# main.net
KiCad netlist of a schematic drawn in EAGLE
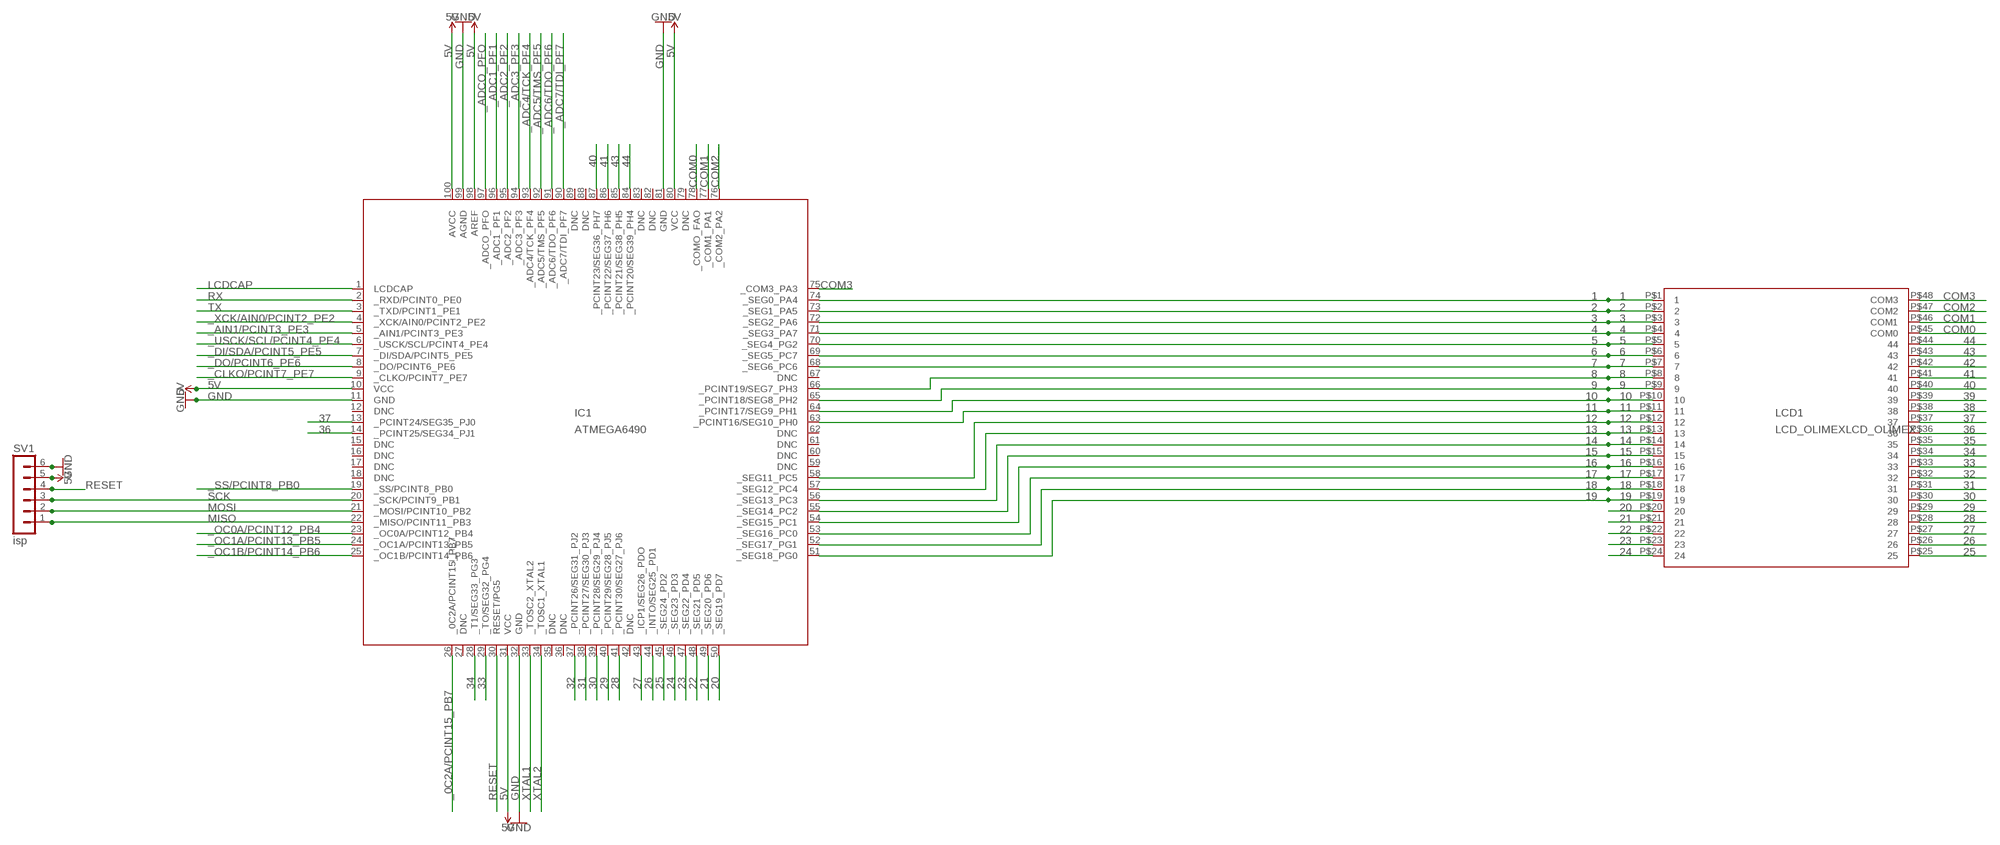
[diagram p0: schematic, sheet 1]

(export (version "E")
  (design (tool "Eeschema 10.0.6"))
  (components
    (comp (ref "IC1")
      (value "ATMEGA6490")
      (footprint "eagle-import:TQFP100")
      (libsource (lib "eagle-import") (part "ATMEGA6490"))
    )
    (comp (ref "LCD1")
      (value "LCD_OLIMEXLCD_OLIMEX")
      (footprint "eagle-import:LCD_OLIMEX")
      (libsource (lib "eagle-import") (part "LCD_OLIMEXLCD_OLIMEX"))
    )
    (comp (ref "SV1")
      (value "isp")
      (footprint "eagle-import:MA06-1")
      (libsource (lib "eagle-import") (part "MA06-1"))
    )
  )
  (nets
    (net (code "1") (name "/1") (class "Default")
      (node (ref "IC1") (pin "74") (pinfunction "_SEG0_PA4_74") (pintype "bidirectional"))
      (node (ref "LCD1") (pin "P$1") (pinfunction "1_P$1") (pintype "bidirectional"))
    )
    (net (code "2") (name "/2") (class "Default")
      (node (ref "IC1") (pin "73") (pinfunction "_SEG1_PA5_73") (pintype "bidirectional"))
      (node (ref "LCD1") (pin "P$2") (pinfunction "2_P$2") (pintype "bidirectional"))
    )
    (net (code "3") (name "/3") (class "Default")
      (node (ref "IC1") (pin "72") (pinfunction "_SEG2_PA6_72") (pintype "bidirectional"))
      (node (ref "LCD1") (pin "P$3") (pinfunction "3_P$3") (pintype "bidirectional"))
    )
    (net (code "4") (name "/4") (class "Default")
      (node (ref "IC1") (pin "71") (pinfunction "_SEG3_PA7_71") (pintype "bidirectional"))
      (node (ref "LCD1") (pin "P$4") (pinfunction "4_P$4") (pintype "bidirectional"))
    )
    (net (code "5") (name "/5") (class "Default")
      (node (ref "IC1") (pin "70") (pinfunction "_SEG4_PG2_70") (pintype "bidirectional"))
      (node (ref "LCD1") (pin "P$5") (pinfunction "5_P$5") (pintype "bidirectional"))
    )
    (net (code "6") (name "/6") (class "Default")
      (node (ref "IC1") (pin "69") (pinfunction "_SEG5_PC7_69") (pintype "bidirectional"))
      (node (ref "LCD1") (pin "P$6") (pinfunction "6_P$6") (pintype "bidirectional"))
    )
    (net (code "7") (name "/7") (class "Default")
      (node (ref "IC1") (pin "68") (pinfunction "_SEG6_PC6_68") (pintype "bidirectional"))
      (node (ref "LCD1") (pin "P$7") (pinfunction "7_P$7") (pintype "bidirectional"))
    )
    (net (code "8") (name "/8") (class "Default")
      (node (ref "IC1") (pin "66") (pinfunction "_PCINT19/SEG7_PH3_66") (pintype "bidirectional"))
      (node (ref "LCD1") (pin "P$8") (pinfunction "8_P$8") (pintype "bidirectional"))
    )
    (net (code "9") (name "/9") (class "Default")
      (node (ref "IC1") (pin "65") (pinfunction "_PCINT18/SEG8_PH2_65") (pintype "bidirectional"))
      (node (ref "LCD1") (pin "P$9") (pinfunction "9_P$9") (pintype "bidirectional"))
    )
    (net (code "10") (name "/10") (class "Default")
      (node (ref "IC1") (pin "64") (pinfunction "_PCINT17/SEG9_PH1_64") (pintype "bidirectional"))
      (node (ref "LCD1") (pin "P$10") (pinfunction "10_P$10") (pintype "bidirectional"))
    )
    (net (code "11") (name "/11") (class "Default")
      (node (ref "IC1") (pin "63") (pinfunction "_PCINT16/SEG10_PH0_63") (pintype "bidirectional"))
      (node (ref "LCD1") (pin "P$11") (pinfunction "11_P$11") (pintype "bidirectional"))
    )
    (net (code "12") (name "/12") (class "Default")
      (node (ref "IC1") (pin "58") (pinfunction "_SEG11_PC5_58") (pintype "bidirectional"))
      (node (ref "LCD1") (pin "P$12") (pinfunction "12_P$12") (pintype "bidirectional"))
    )
    (net (code "13") (name "/13") (class "Default")
      (node (ref "IC1") (pin "57") (pinfunction "_SEG12_PC4_57") (pintype "bidirectional"))
      (node (ref "LCD1") (pin "P$13") (pinfunction "13_P$13") (pintype "bidirectional"))
    )
    (net (code "14") (name "/14") (class "Default")
      (node (ref "IC1") (pin "56") (pinfunction "_SEG13_PC3_56") (pintype "bidirectional"))
      (node (ref "LCD1") (pin "P$14") (pinfunction "14_P$14") (pintype "bidirectional"))
    )
    (net (code "15") (name "/15") (class "Default")
      (node (ref "IC1") (pin "55") (pinfunction "_SEG14_PC2_55") (pintype "bidirectional"))
      (node (ref "LCD1") (pin "P$15") (pinfunction "15_P$15") (pintype "bidirectional"))
    )
    (net (code "16") (name "/16") (class "Default")
      (node (ref "IC1") (pin "54") (pinfunction "_SEG15_PC1_54") (pintype "bidirectional"))
      (node (ref "LCD1") (pin "P$16") (pinfunction "16_P$16") (pintype "bidirectional"))
    )
    (net (code "17") (name "/17") (class "Default")
      (node (ref "IC1") (pin "53") (pinfunction "_SEG16_PC0_53") (pintype "bidirectional"))
      (node (ref "LCD1") (pin "P$17") (pinfunction "17_P$17") (pintype "bidirectional"))
    )
    (net (code "18") (name "/18") (class "Default")
      (node (ref "IC1") (pin "52") (pinfunction "_SEG17_PG1_52") (pintype "bidirectional"))
      (node (ref "LCD1") (pin "P$18") (pinfunction "18_P$18") (pintype "bidirectional"))
    )
    (net (code "19") (name "/19") (class "Default")
      (node (ref "IC1") (pin "51") (pinfunction "_SEG18_PG0_51") (pintype "bidirectional"))
      (node (ref "LCD1") (pin "P$19") (pinfunction "19_P$19") (pintype "bidirectional"))
    )
    (net (code "20") (name "/20") (class "Default")
      (node (ref "IC1") (pin "50") (pinfunction "_SEG19_PD7_50") (pintype "bidirectional"))
      (node (ref "LCD1") (pin "P$20") (pinfunction "20_P$20") (pintype "bidirectional"))
    )
    (net (code "21") (name "/21") (class "Default")
      (node (ref "IC1") (pin "49") (pinfunction "_SEG20_PD6_49") (pintype "bidirectional"))
      (node (ref "LCD1") (pin "P$21") (pinfunction "21_P$21") (pintype "bidirectional"))
    )
    (net (code "22") (name "/22") (class "Default")
      (node (ref "IC1") (pin "48") (pinfunction "_SEG21_PD5_48") (pintype "bidirectional"))
      (node (ref "LCD1") (pin "P$22") (pinfunction "22_P$22") (pintype "bidirectional"))
    )
    (net (code "23") (name "/23") (class "Default")
      (node (ref "IC1") (pin "47") (pinfunction "_SEG22_PD4_47") (pintype "bidirectional"))
      (node (ref "LCD1") (pin "P$23") (pinfunction "23_P$23") (pintype "bidirectional"))
    )
    (net (code "24") (name "/24") (class "Default")
      (node (ref "IC1") (pin "46") (pinfunction "_SEG23_PD3_46") (pintype "bidirectional"))
      (node (ref "LCD1") (pin "P$24") (pinfunction "24_P$24") (pintype "bidirectional"))
    )
    (net (code "25") (name "/25") (class "Default")
      (node (ref "IC1") (pin "45") (pinfunction "_SEG24_PD2_45") (pintype "bidirectional"))
      (node (ref "LCD1") (pin "P$25") (pinfunction "25_P$25") (pintype "bidirectional"))
    )
    (net (code "26") (name "/26") (class "Default")
      (node (ref "IC1") (pin "44") (pinfunction "_INTO/SEG25_PD1_44") (pintype "bidirectional"))
      (node (ref "LCD1") (pin "P$26") (pinfunction "26_P$26") (pintype "bidirectional"))
    )
    (net (code "27") (name "/27") (class "Default")
      (node (ref "IC1") (pin "43") (pinfunction "_ICP1/SEG26_PDO_43") (pintype "bidirectional"))
      (node (ref "LCD1") (pin "P$27") (pinfunction "27_P$27") (pintype "bidirectional"))
    )
    (net (code "28") (name "/28") (class "Default")
      (node (ref "IC1") (pin "41") (pinfunction "_PCINT30/SEG27_PJ6_41") (pintype "bidirectional"))
      (node (ref "LCD1") (pin "P$28") (pinfunction "28_P$28") (pintype "bidirectional"))
    )
    (net (code "29") (name "/29") (class "Default")
      (node (ref "IC1") (pin "40") (pinfunction "_PCINT29/SEG28_PJ5_40") (pintype "bidirectional"))
      (node (ref "LCD1") (pin "P$29") (pinfunction "29_P$29") (pintype "bidirectional"))
    )
    (net (code "30") (name "/30") (class "Default")
      (node (ref "IC1") (pin "39") (pinfunction "_PCINT28/SEG29_PJ4_39") (pintype "bidirectional"))
      (node (ref "LCD1") (pin "P$30") (pinfunction "30_P$30") (pintype "bidirectional"))
    )
    (net (code "31") (name "/31") (class "Default")
      (node (ref "IC1") (pin "38") (pinfunction "_PCINT27/SEG30_PJ3_38") (pintype "bidirectional"))
      (node (ref "LCD1") (pin "P$31") (pinfunction "31_P$31") (pintype "bidirectional"))
    )
    (net (code "32") (name "/32") (class "Default")
      (node (ref "IC1") (pin "37") (pinfunction "_PCINT26/SEG31_PJ2_37") (pintype "bidirectional"))
      (node (ref "LCD1") (pin "P$32") (pinfunction "32_P$32") (pintype "bidirectional"))
    )
    (net (code "33") (name "/33") (class "Default")
      (node (ref "IC1") (pin "29") (pinfunction "_TO/SEG32_PG4_29") (pintype "bidirectional"))
      (node (ref "LCD1") (pin "P$33") (pinfunction "33_P$33") (pintype "bidirectional"))
    )
    (net (code "34") (name "/34") (class "Default")
      (node (ref "IC1") (pin "28") (pinfunction "_T1/SEG33_PG3_28") (pintype "bidirectional"))
      (node (ref "LCD1") (pin "P$34") (pinfunction "34_P$34") (pintype "bidirectional"))
    )
    (net (code "35") (name "/35") (class "Default")
      (node (ref "LCD1") (pin "P$35") (pinfunction "35_P$35") (pintype "bidirectional"))
    )
    (net (code "36") (name "/36") (class "Default")
      (node (ref "IC1") (pin "14") (pinfunction "_PCINT25/SEG34_PJ1_14") (pintype "bidirectional"))
      (node (ref "LCD1") (pin "P$36") (pinfunction "36_P$36") (pintype "bidirectional"))
    )
    (net (code "37") (name "/37") (class "Default")
      (node (ref "IC1") (pin "13") (pinfunction "_PCINT24/SEG35_PJ0_13") (pintype "bidirectional"))
      (node (ref "LCD1") (pin "P$37") (pinfunction "37_P$37") (pintype "bidirectional"))
    )
    (net (code "38") (name "/38") (class "Default")
      (node (ref "LCD1") (pin "P$38") (pinfunction "38_P$38") (pintype "bidirectional"))
    )
    (net (code "39") (name "/39") (class "Default")
      (node (ref "LCD1") (pin "P$39") (pinfunction "39_P$39") (pintype "bidirectional"))
    )
    (net (code "40") (name "/40") (class "Default")
      (node (ref "IC1") (pin "87") (pinfunction "_PCINT23/SEG36_PH7_87") (pintype "bidirectional"))
      (node (ref "LCD1") (pin "P$40") (pinfunction "40_P$40") (pintype "bidirectional"))
    )
    (net (code "41") (name "/41") (class "Default")
      (node (ref "IC1") (pin "86") (pinfunction "_PCINT22/SEG37_PH6_86") (pintype "bidirectional"))
      (node (ref "LCD1") (pin "P$41") (pinfunction "41_P$41") (pintype "bidirectional"))
    )
    (net (code "42") (name "/42") (class "Default")
      (node (ref "LCD1") (pin "P$42") (pinfunction "42_P$42") (pintype "bidirectional"))
    )
    (net (code "43") (name "/43") (class "Default")
      (node (ref "IC1") (pin "85") (pinfunction "_PCINT21/SEG38_PH5_85") (pintype "bidirectional"))
      (node (ref "LCD1") (pin "P$43") (pinfunction "43_P$43") (pintype "bidirectional"))
    )
    (net (code "44") (name "/44") (class "Default")
      (node (ref "IC1") (pin "84") (pinfunction "_PCINT20/SEG39_PH4_84") (pintype "bidirectional"))
      (node (ref "LCD1") (pin "P$44") (pinfunction "44_P$44") (pintype "bidirectional"))
    )
    (net (code "45") (name "/COM0") (class "Default")
      (node (ref "IC1") (pin "78") (pinfunction "_COMO_FAO_78") (pintype "bidirectional"))
      (node (ref "LCD1") (pin "P$45") (pinfunction "COM0_P$45") (pintype "bidirectional"))
    )
    (net (code "46") (name "/COM1") (class "Default")
      (node (ref "IC1") (pin "77") (pinfunction "_COM1_PA1_77") (pintype "bidirectional"))
      (node (ref "LCD1") (pin "P$46") (pinfunction "COM1_P$46") (pintype "bidirectional"))
    )
    (net (code "47") (name "/COM2") (class "Default")
      (node (ref "IC1") (pin "76") (pinfunction "_COM2_PA2_76") (pintype "bidirectional"))
      (node (ref "LCD1") (pin "P$47") (pinfunction "COM2_P$47") (pintype "bidirectional"))
    )
    (net (code "48") (name "/COM3") (class "Default")
      (node (ref "IC1") (pin "75") (pinfunction "_COM3_PA3_75") (pintype "bidirectional"))
      (node (ref "LCD1") (pin "P$48") (pinfunction "COM3_P$48") (pintype "bidirectional"))
    )
    (net (code "49") (name "/LCDCAP") (class "Default")
      (node (ref "IC1") (pin "1") (pinfunction "LCDCAP_1") (pintype "bidirectional"))
    )
    (net (code "50") (name "/MISO") (class "Default")
      (node (ref "IC1") (pin "22") (pinfunction "_MISO/PCINT11_PB3_22") (pintype "bidirectional"))
      (node (ref "SV1") (pin "1") (pinfunction "1_1") (pintype "passive"))
    )
    (net (code "51") (name "/MOSI") (class "Default")
      (node (ref "IC1") (pin "21") (pinfunction "_MOSI/PCINT10_PB2_21") (pintype "bidirectional"))
      (node (ref "SV1") (pin "2") (pinfunction "2_2") (pintype "passive"))
    )
    (net (code "52") (name "/RESET") (class "Default")
      (node (ref "IC1") (pin "30") (pinfunction "RESET/PG5_30") (pintype "bidirectional"))
      (node (ref "SV1") (pin "4") (pinfunction "4_4") (pintype "passive"))
    )
    (net (code "53") (name "/RX") (class "Default")
      (node (ref "IC1") (pin "2") (pinfunction "_RXD/PCINT0_PE0_2") (pintype "bidirectional"))
    )
    (net (code "54") (name "/SCK") (class "Default")
      (node (ref "IC1") (pin "20") (pinfunction "_SCK/PCINT9_PB1_20") (pintype "bidirectional"))
      (node (ref "SV1") (pin "3") (pinfunction "3_3") (pintype "passive"))
    )
    (net (code "55") (name "/TX") (class "Default")
      (node (ref "IC1") (pin "3") (pinfunction "_TXD/PCINT1_PE1_3") (pintype "bidirectional"))
    )
    (net (code "56") (name "/XTAL1") (class "Default")
      (node (ref "IC1") (pin "33") (pinfunction "_TOSC2_XTAL2_33") (pintype "bidirectional"))
    )
    (net (code "57") (name "/XTAL2") (class "Default")
      (node (ref "IC1") (pin "34") (pinfunction "_TOSC1_XTAL1_34") (pintype "bidirectional"))
    )
    (net (code "58") (name "/_0C2A{slash}PCINT15_PB7") (class "Default")
      (node (ref "IC1") (pin "26") (pinfunction "_0C2A/PCINT15_PB7_26") (pintype "bidirectional"))
    )
    (net (code "59") (name "/_ADC1_PF1") (class "Default")
      (node (ref "IC1") (pin "96") (pinfunction "_ADC1_PF1_96") (pintype "bidirectional"))
    )
    (net (code "60") (name "/_ADC2_PF2") (class "Default")
      (node (ref "IC1") (pin "95") (pinfunction "_ADC2_PF2_95") (pintype "bidirectional"))
    )
    (net (code "61") (name "/_ADC3_PF3") (class "Default")
      (node (ref "IC1") (pin "94") (pinfunction "_ADC3_PF3_94") (pintype "bidirectional"))
    )
    (net (code "62") (name "/_ADC4{slash}TCK_PF4") (class "Default")
      (node (ref "IC1") (pin "93") (pinfunction "_ADC4/TCK_PF4_93") (pintype "bidirectional"))
    )
    (net (code "63") (name "/_ADC5{slash}TMS_PF5") (class "Default")
      (node (ref "IC1") (pin "92") (pinfunction "_ADC5/TMS_PF5_92") (pintype "bidirectional"))
    )
    (net (code "64") (name "/_ADC6{slash}TDO_PF6") (class "Default")
      (node (ref "IC1") (pin "91") (pinfunction "_ADC6/TDO_PF6_91") (pintype "bidirectional"))
    )
    (net (code "65") (name "/_ADC7{slash}TDI_PF7") (class "Default")
      (node (ref "IC1") (pin "90") (pinfunction "_ADC7/TDI_PF7_90") (pintype "bidirectional"))
    )
    (net (code "66") (name "/_ADCO_PFO") (class "Default")
      (node (ref "IC1") (pin "97") (pinfunction "_ADCO_PFO_97") (pintype "bidirectional"))
    )
    (net (code "67") (name "/_AIN1{slash}PCINT3_PE3") (class "Default")
      (node (ref "IC1") (pin "5") (pinfunction "_AIN1/PCINT3_PE3_5") (pintype "bidirectional"))
    )
    (net (code "68") (name "/_CLKO{slash}PCINT7_PE7") (class "Default")
      (node (ref "IC1") (pin "9") (pinfunction "_CLKO/PCINT7_PE7_9") (pintype "bidirectional"))
    )
    (net (code "69") (name "/_DI{slash}SDA{slash}PCINT5_PE5") (class "Default")
      (node (ref "IC1") (pin "7") (pinfunction "_DI/SDA/PCINT5_PE5_7") (pintype "bidirectional"))
    )
    (net (code "70") (name "/_DO{slash}PCINT6_PE6") (class "Default")
      (node (ref "IC1") (pin "8") (pinfunction "_DO/PCINT6_PE6_8") (pintype "bidirectional"))
    )
    (net (code "71") (name "/_OC0A{slash}PCINT12_PB4") (class "Default")
      (node (ref "IC1") (pin "23") (pinfunction "_OC0A/PCINT12_PB4_23") (pintype "bidirectional"))
    )
    (net (code "72") (name "/_OC1A{slash}PCINT13_PB5") (class "Default")
      (node (ref "IC1") (pin "24") (pinfunction "_OC1A/PCINT13_PB5_24") (pintype "bidirectional"))
    )
    (net (code "73") (name "/_OC1B{slash}PCINT14_PB6") (class "Default")
      (node (ref "IC1") (pin "25") (pinfunction "_OC1B/PCINT14_PB6_25") (pintype "bidirectional"))
    )
    (net (code "74") (name "/_SS{slash}PCINT8_PB0") (class "Default")
      (node (ref "IC1") (pin "19") (pinfunction "_SS/PCINT8_PB0_19") (pintype "bidirectional"))
    )
    (net (code "75") (name "/_USCK{slash}SCL{slash}PCINT4_PE4") (class "Default")
      (node (ref "IC1") (pin "6") (pinfunction "_USCK/SCL/PCINT4_PE4_6") (pintype "bidirectional"))
    )
    (net (code "76") (name "/_XCK{slash}AIN0{slash}PCINT2_PE2") (class "Default")
      (node (ref "IC1") (pin "4") (pinfunction "_XCK/AIN0/PCINT2_PE2_4") (pintype "bidirectional"))
    )
    (net (code "77") (name "5V") (class "Default")
      (node (ref "IC1") (pin "10") (pinfunction "VCC_10") (pintype "bidirectional"))
      (node (ref "IC1") (pin "100") (pinfunction "AVCC_100") (pintype "bidirectional"))
      (node (ref "IC1") (pin "31") (pinfunction "VCC_31") (pintype "bidirectional"))
      (node (ref "IC1") (pin "80") (pinfunction "VCC_80") (pintype "bidirectional"))
      (node (ref "IC1") (pin "98") (pinfunction "AREF_98") (pintype "bidirectional"))
      (node (ref "SV1") (pin "5") (pinfunction "5_5") (pintype "passive"))
    )
    (net (code "78") (name "GND") (class "Default")
      (node (ref "IC1") (pin "11") (pinfunction "GND_11") (pintype "bidirectional"))
      (node (ref "IC1") (pin "32") (pinfunction "GND_32") (pintype "bidirectional"))
      (node (ref "IC1") (pin "81") (pinfunction "GND_81") (pintype "bidirectional"))
      (node (ref "IC1") (pin "99") (pinfunction "AGND_99") (pintype "bidirectional"))
      (node (ref "SV1") (pin "6") (pinfunction "6_6") (pintype "passive"))
    )
    (net (code "79") (name "unconnected-(IC1-DNC-Pad12)") (class "Default")
      (node (ref "IC1") (pin "12") (pinfunction "DNC_12") (pintype "bidirectional"))
    )
    (net (code "80") (name "unconnected-(IC1-DNC-Pad15)") (class "Default")
      (node (ref "IC1") (pin "15") (pinfunction "DNC_15") (pintype "bidirectional"))
    )
    (net (code "81") (name "unconnected-(IC1-DNC-Pad16)") (class "Default")
      (node (ref "IC1") (pin "16") (pinfunction "DNC_16") (pintype "bidirectional"))
    )
    (net (code "82") (name "unconnected-(IC1-DNC-Pad17)") (class "Default")
      (node (ref "IC1") (pin "17") (pinfunction "DNC_17") (pintype "bidirectional"))
    )
    (net (code "83") (name "unconnected-(IC1-DNC-Pad18)") (class "Default")
      (node (ref "IC1") (pin "18") (pinfunction "DNC_18") (pintype "bidirectional"))
    )
    (net (code "84") (name "unconnected-(IC1-DNC-Pad27)") (class "Default")
      (node (ref "IC1") (pin "27") (pinfunction "DNC_27") (pintype "bidirectional"))
    )
    (net (code "85") (name "unconnected-(IC1-DNC-Pad35)") (class "Default")
      (node (ref "IC1") (pin "35") (pinfunction "DNC_35") (pintype "bidirectional"))
    )
    (net (code "86") (name "unconnected-(IC1-DNC-Pad36)") (class "Default")
      (node (ref "IC1") (pin "36") (pinfunction "DNC_36") (pintype "bidirectional"))
    )
    (net (code "87") (name "unconnected-(IC1-DNC-Pad42)") (class "Default")
      (node (ref "IC1") (pin "42") (pinfunction "DNC_42") (pintype "bidirectional"))
    )
    (net (code "88") (name "unconnected-(IC1-DNC-Pad59)") (class "Default")
      (node (ref "IC1") (pin "59") (pinfunction "DNC_59") (pintype "bidirectional"))
    )
    (net (code "89") (name "unconnected-(IC1-DNC-Pad60)") (class "Default")
      (node (ref "IC1") (pin "60") (pinfunction "DNC_60") (pintype "bidirectional"))
    )
    (net (code "90") (name "unconnected-(IC1-DNC-Pad61)") (class "Default")
      (node (ref "IC1") (pin "61") (pinfunction "DNC_61") (pintype "bidirectional"))
    )
    (net (code "91") (name "unconnected-(IC1-DNC-Pad62)") (class "Default")
      (node (ref "IC1") (pin "62") (pinfunction "DNC_62") (pintype "bidirectional"))
    )
    (net (code "92") (name "unconnected-(IC1-DNC-Pad67)") (class "Default")
      (node (ref "IC1") (pin "67") (pinfunction "DNC_67") (pintype "bidirectional"))
    )
    (net (code "93") (name "unconnected-(IC1-DNC-Pad79)") (class "Default")
      (node (ref "IC1") (pin "79") (pinfunction "DNC_79") (pintype "bidirectional"))
    )
    (net (code "94") (name "unconnected-(IC1-DNC-Pad82)") (class "Default")
      (node (ref "IC1") (pin "82") (pinfunction "DNC_82") (pintype "bidirectional"))
    )
    (net (code "95") (name "unconnected-(IC1-DNC-Pad83)") (class "Default")
      (node (ref "IC1") (pin "83") (pinfunction "DNC_83") (pintype "bidirectional"))
    )
    (net (code "96") (name "unconnected-(IC1-DNC-Pad88)") (class "Default")
      (node (ref "IC1") (pin "88") (pinfunction "DNC_88") (pintype "bidirectional"))
    )
    (net (code "97") (name "unconnected-(IC1-DNC-Pad89)") (class "Default")
      (node (ref "IC1") (pin "89") (pinfunction "DNC_89") (pintype "bidirectional"))
    )
  )
)
